# GPS_NEO.net
KiCad netlist of a schematic drawn in Altium Designer
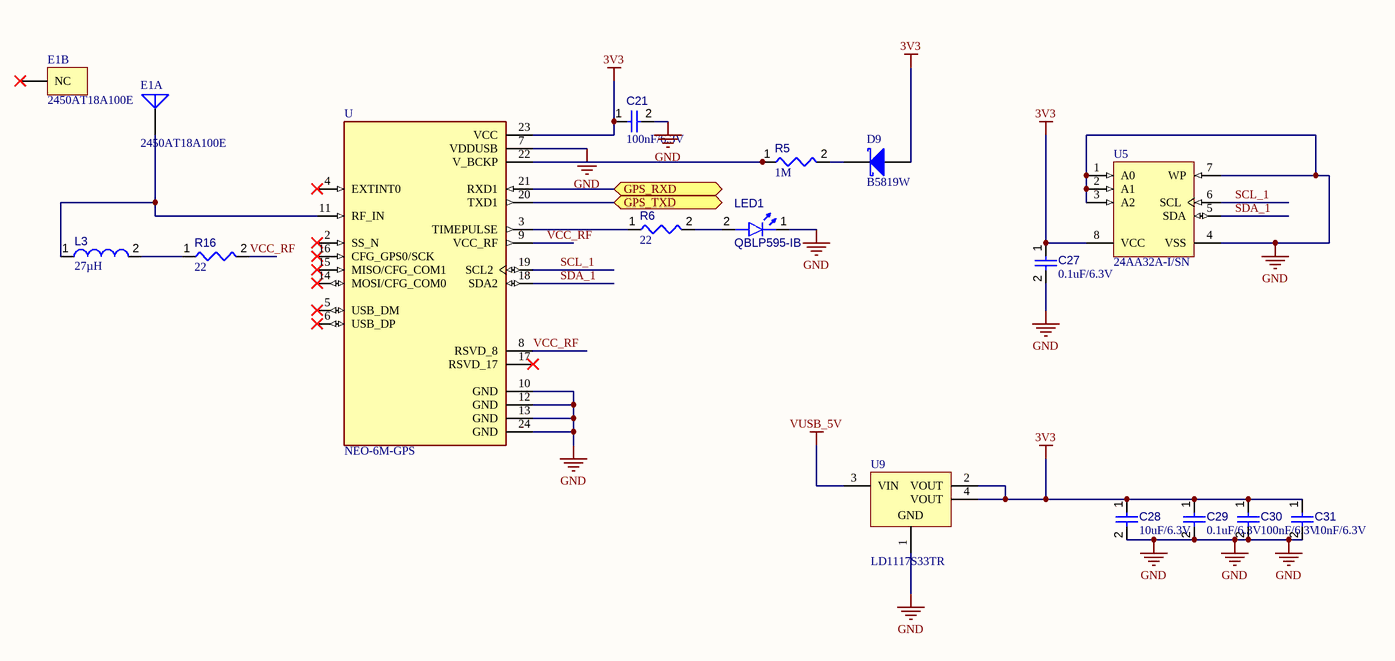
[diagram p0: GPS_NEO.SchDoc]

(export (version "E")
  (design (tool "Eeschema 10.0.6"))
  (components
    (comp (ref "C21")
      (value "100nF/6.3V")
      (footprint "CAPC0402(1005)60_L")
      (description "Chip Capacitor, 220nF +/-20%, 10V, 0402, Thickness 0.6 mm")
      (fields (field (name "TOLERANCE") "10%") (field (name "Comment") "Capacitor 220nF +/-20% 10V 0402"))
      (libsource (lib "Kenyatta University") (part "CAP-NP-2"))
    )
    (comp (ref "C27")
      (value "0.1uF/6.3V")
      (footprint "CAPC0402(1005)60_L")
      (description "Chip Capacitor, 220nF +/-20%, 10V, 0402, Thickness 0.6 mm")
      (fields (field (name "TOLERANCE") "10%") (field (name "Comment") "Capacitor 220nF +/-20% 10V 0402"))
      (libsource (lib "Kenyatta University") (part "CAP-NP-2"))
    )
    (comp (ref "C28")
      (value "10uF/6.3V")
      (footprint "CAPC0402(1005)60_L")
      (description "Chip Capacitor, 220nF +/-20%, 10V, 0402, Thickness 0.6 mm")
      (fields (field (name "TOLERANCE") "10%") (field (name "Comment") "Capacitor 220nF +/-20% 10V 0402"))
      (libsource (lib "Kenyatta University") (part "CAP-NP-2"))
    )
    (comp (ref "C29")
      (value "0.1uF/6.3V")
      (footprint "CAPC0402(1005)60_L")
      (description "Chip Capacitor, 220nF +/-20%, 10V, 0402, Thickness 0.6 mm")
      (fields (field (name "TOLERANCE") "10%") (field (name "Comment") "Capacitor 220nF +/-20% 10V 0402"))
      (libsource (lib "Kenyatta University") (part "CAP-NP-2"))
    )
    (comp (ref "C30")
      (value "100nF/6.3V")
      (footprint "CAPC0402(1005)60_L")
      (description "Chip Capacitor, 220nF +/-20%, 10V, 0402, Thickness 0.6 mm")
      (fields (field (name "TOLERANCE") "10%") (field (name "Comment") "Capacitor 220nF +/-20% 10V 0402"))
      (libsource (lib "Kenyatta University") (part "CAP-NP-2"))
    )
    (comp (ref "C31")
      (value "10nF/6.3V")
      (footprint "CAPC0402(1005)60_L")
      (description "Chip Capacitor, 220nF +/-20%, 10V, 0402, Thickness 0.6 mm")
      (fields (field (name "TOLERANCE") "10%") (field (name "Comment") "Capacitor 220nF +/-20% 10V 0402"))
      (libsource (lib "Kenyatta University") (part "CAP-NP-2"))
    )
    (comp (ref "D9")
      (value "B5819W")
      (footprint "MCC-SOD123_V")
      (description "Schottky Barrier Rectifier, 40 V, 1 A, -65 to 125 degC, 2-Pin SOD123, RoHS, Tape and Reel")
      (fields (field (name "MANUFACTURER") "Micro Commercial Components"))
      (libsource (lib "Kenyatta University") (part "DSKY-AK-2"))
    )
    (comp (ref "E1")
      (value "2450AT18A100E")
      (footprint "JT-2450AT18A100-2_V")
      (description "Ceramic Antenna, 2.45 GHZ, 2 W, -40 to 125 degC, 2-Pin SMD, RoHS, Tape and Reel")
      (fields (field (name "MANUFACTURER") "Johanson Technology"))
      (libsource (lib "ANTENNA") (part "CMP-2000-05167-1"))
    )
    (comp (ref "L3")
      (value "27µH")
      (footprint "IND1005X55X20VL5T10")
      (description "Chip Inductor, 2.2 nH, +/- 0.3 nH, 400 mA, -40 to 85 degC, 0402 (1005 Metric), RoHS, Tape and Reel")
      (fields (field (name "TOLERANCE") "5%") (field (name "MANUFACTURER") "Panasonic"))
      (libsource (lib "Kenyatta University") (part "IND-2"))
    )
    (comp (ref "LED1")
      (value "QBLP595-IB")
      (footprint "QTB-QBLP595_V")
      (description "Chip LED 0402, Blue, 0.02 A, 3.1 to 3.7 V, -40 to 80 degC, 2-Pin SMD, RoHS, Tape and Reel")
      (libsource (lib "Kenyatta University") (part "LED-KA-2"))
    )
    (comp (ref "R5")
      (value "1M")
      (footprint "RESC0402(1005)_L")
      (description "Chip Resistor, 1 MOhms, +/-5 %, 63 mW, -55 to 155 degC, 0402")
      (fields (field (name "POWER") "63mW") (field (name "TOLERANCE") "5%"))
      (libsource (lib "Kenyatta University") (part "RES-2"))
    )
    (comp (ref "R6")
      (value "22")
      (footprint "RESC0402(1005)_L")
      (description "Chip Resistor, 22 Ohms, +/-5 %, 63 mW, -55 to 155 degC, 0402")
      (fields (field (name "TOLERANCE") "5%") (field (name "POWER") "63mW"))
      (libsource (lib "Kenyatta University") (part "RES-2"))
    )
    (comp (ref "R16")
      (value "22")
      (footprint "RESC0402(1005)_L")
      (description "Chip Resistor, 22 Ohms, +/-5 %, 63 mW, -55 to 155 degC, 0402")
      (fields (field (name "TOLERANCE") "5%") (field (name "POWER") "63mW"))
      (libsource (lib "Kenyatta University") (part "RES-2"))
    )
    (comp (ref "U")
      (value "NEO-6M-GPS")
      (footprint "XCVR_NEO-6M-GPS")
      (description "SMD GPS Module;")
      (fields (field (name "MF") "u-blox"))
      (libsource (lib "NEO-6M-GPS") (part "NEO-6M-GPS"))
    )
    (comp (ref "U5")
      (value "24AA32A-I/SN")
      (footprint "SOIC-SN8_N")
      (description "32Kbit, 400kHz, 1.7V, I2C Serial EEPROM, 8-Pin SOIC 150mil, Industrial Temperature")
      (libsource (lib "24AAA32A") (part "CMP-0159-00205-1"))
    )
    (comp (ref "U9")
      (value "LD1117S33TR")
      (footprint "STM-SOT-223_M")
      (fields (field (name "MANUFACTURER") "STMicroelectronics") (field (name "POWER") "12W"))
      (libsource (lib "Kenyatta University") (part "STM-LD1117-SOT223-4"))
    )
  )
  (nets
    (net (code "1") (name "/GPS_RXD") (class "Default")
      (node (ref "U") (pin "21") (pinfunction "RXD1_21") (pintype "input"))
    )
    (net (code "2") (name "/GPS_TXD") (class "Default")
      (node (ref "U") (pin "20") (pinfunction "TXD1_20") (pintype "output"))
    )
    (net (code "3") (name "/SCL_1") (class "Default")
      (node (ref "U") (pin "19") (pinfunction "SCL2_19") (pintype "bidirectional"))
      (node (ref "U5") (pin "6") (pinfunction "SCL_6") (pintype "input"))
    )
    (net (code "4") (name "/SDA_1") (class "Default")
      (node (ref "U") (pin "18") (pinfunction "SDA2_18") (pintype "bidirectional"))
      (node (ref "U5") (pin "5") (pinfunction "SDA_5") (pintype "bidirectional"))
    )
    (net (code "5") (name "/VCC_RF") (class "Default")
      (node (ref "R16") (pin "2") (pinfunction "2_2") (pintype "passive"))
      (node (ref "U") (pin "8") (pinfunction "RSVD_8_8") (pintype "passive"))
      (node (ref "U") (pin "9") (pinfunction "VCC_RF_9") (pintype "output"))
    )
    (net (code "6") (name "3V3") (class "Default")
      (node (ref "C21") (pin "1") (pinfunction "1_1") (pintype "passive"))
      (node (ref "C27") (pin "1") (pinfunction "1_1") (pintype "passive"))
      (node (ref "C28") (pin "1") (pinfunction "1_1") (pintype "passive"))
      (node (ref "C29") (pin "1") (pinfunction "1_1") (pintype "passive"))
      (node (ref "C30") (pin "1") (pinfunction "1_1") (pintype "passive"))
      (node (ref "C31") (pin "1") (pinfunction "1_1") (pintype "passive"))
      (node (ref "D9") (pin "1") (pinfunction "A_1") (pintype "passive"))
      (node (ref "U") (pin "23") (pinfunction "VCC_23") (pintype "power_in"))
      (node (ref "U5") (pin "8") (pinfunction "VCC_8") (pintype "power_in"))
      (node (ref "U9") (pin "2") (pinfunction "VOUT_2") (pintype "power_in"))
      (node (ref "U9") (pin "4") (pinfunction "VOUT_4") (pintype "power_in"))
    )
    (net (code "7") (name "GND") (class "Default")
      (node (ref "C21") (pin "2") (pinfunction "2_2") (pintype "passive"))
      (node (ref "C27") (pin "2") (pinfunction "2_2") (pintype "passive"))
      (node (ref "C28") (pin "2") (pinfunction "2_2") (pintype "passive"))
      (node (ref "C29") (pin "2") (pinfunction "2_2") (pintype "passive"))
      (node (ref "C30") (pin "2") (pinfunction "2_2") (pintype "passive"))
      (node (ref "C31") (pin "2") (pinfunction "2_2") (pintype "passive"))
      (node (ref "LED1") (pin "1") (pinfunction "K_1") (pintype "passive"))
      (node (ref "U") (pin "10") (pinfunction "GND_10") (pintype "power_in"))
      (node (ref "U") (pin "12") (pinfunction "GND_12") (pintype "power_in"))
      (node (ref "U") (pin "13") (pinfunction "GND_13") (pintype "power_in"))
      (node (ref "U") (pin "24") (pinfunction "GND_24") (pintype "power_in"))
      (node (ref "U") (pin "7") (pinfunction "VDDUSB_7") (pintype "power_in"))
      (node (ref "U5") (pin "1") (pinfunction "A0_1") (pintype "input"))
      (node (ref "U5") (pin "2") (pinfunction "A1_2") (pintype "input"))
      (node (ref "U5") (pin "3") (pinfunction "A2_3") (pintype "input"))
      (node (ref "U5") (pin "4") (pinfunction "VSS_4") (pintype "power_in"))
      (node (ref "U5") (pin "7") (pinfunction "WP_7") (pintype "input"))
      (node (ref "U9") (pin "1") (pinfunction "GND_1") (pintype "power_in"))
    )
    (net (code "8") (name "Net-(D9-K)") (class "Default")
      (node (ref "D9") (pin "2") (pinfunction "K_2") (pintype "passive"))
      (node (ref "R5") (pin "2") (pinfunction "2_2") (pintype "passive"))
    )
    (net (code "9") (name "Net-(E1A-FP)") (class "Default")
      (node (ref "E1") (pin "1") (pinfunction "FP_1") (pintype "passive"))
      (node (ref "L3") (pin "1") (pinfunction "1_1") (pintype "passive"))
      (node (ref "U") (pin "11") (pinfunction "RF_IN_11") (pintype "input"))
    )
    (net (code "10") (name "Net-(L3-Pad2)") (class "Default")
      (node (ref "L3") (pin "2") (pinfunction "2_2") (pintype "passive"))
      (node (ref "R16") (pin "1") (pinfunction "1_1") (pintype "passive"))
    )
    (net (code "11") (name "Net-(LED1-A)") (class "Default")
      (node (ref "LED1") (pin "2") (pinfunction "A_2") (pintype "passive"))
      (node (ref "R6") (pin "2") (pinfunction "2_2") (pintype "passive"))
    )
    (net (code "12") (name "Net-(U-TIMEPULSE)") (class "Default")
      (node (ref "R6") (pin "1") (pinfunction "1_1") (pintype "passive"))
      (node (ref "U") (pin "3") (pinfunction "TIMEPULSE_3") (pintype "output"))
    )
    (net (code "13") (name "Net-(U-V_BCKP)") (class "Default")
      (node (ref "R5") (pin "1") (pinfunction "1_1") (pintype "passive"))
      (node (ref "U") (pin "22") (pinfunction "V_BCKP_22") (pintype "power_in"))
    )
    (net (code "14") (name "VUSB_5V") (class "Default")
      (node (ref "U9") (pin "3") (pinfunction "VIN_3") (pintype "power_in"))
    )
    (net (code "15") (name "unconnected-(E1B-NC-Pad2)") (class "Default")
      (node (ref "E1") (pin "2") (pinfunction "NC_2") (pintype "passive+no_connect"))
    )
    (net (code "16") (name "unconnected-(U-CFG_GPS0{slash}SCK-Pad16)") (class "Default")
      (node (ref "U") (pin "16") (pinfunction "CFG_GPS0/SCK_16") (pintype "input+no_connect"))
    )
    (net (code "17") (name "unconnected-(U-EXTINT0-Pad4)") (class "Default")
      (node (ref "U") (pin "4") (pinfunction "EXTINT0_4") (pintype "input+no_connect"))
    )
    (net (code "18") (name "unconnected-(U-MISO{slash}CFG_COM1-Pad15)") (class "Default")
      (node (ref "U") (pin "15") (pinfunction "MISO/CFG_COM1_15") (pintype "input+no_connect"))
    )
    (net (code "19") (name "unconnected-(U-MOSI{slash}CFG_COM0-Pad14)") (class "Default")
      (node (ref "U") (pin "14") (pinfunction "MOSI/CFG_COM0_14") (pintype "bidirectional+no_connect"))
    )
    (net (code "20") (name "unconnected-(U-RSVD_17-Pad17)") (class "Default")
      (node (ref "U") (pin "17") (pinfunction "RSVD_17_17") (pintype "passive+no_connect"))
    )
    (net (code "21") (name "unconnected-(U-SS_N-Pad2)") (class "Default")
      (node (ref "U") (pin "2") (pinfunction "SS_N_2") (pintype "input+no_connect"))
    )
    (net (code "22") (name "unconnected-(U-USB_DM-Pad5)") (class "Default")
      (node (ref "U") (pin "5") (pinfunction "USB_DM_5") (pintype "bidirectional+no_connect"))
    )
    (net (code "23") (name "unconnected-(U-USB_DP-Pad6)") (class "Default")
      (node (ref "U") (pin "6") (pinfunction "USB_DP_6") (pintype "bidirectional+no_connect"))
    )
  )
)
